# dbg-prog-counter.net
KiCad netlist of a schematic drawn in EAGLE
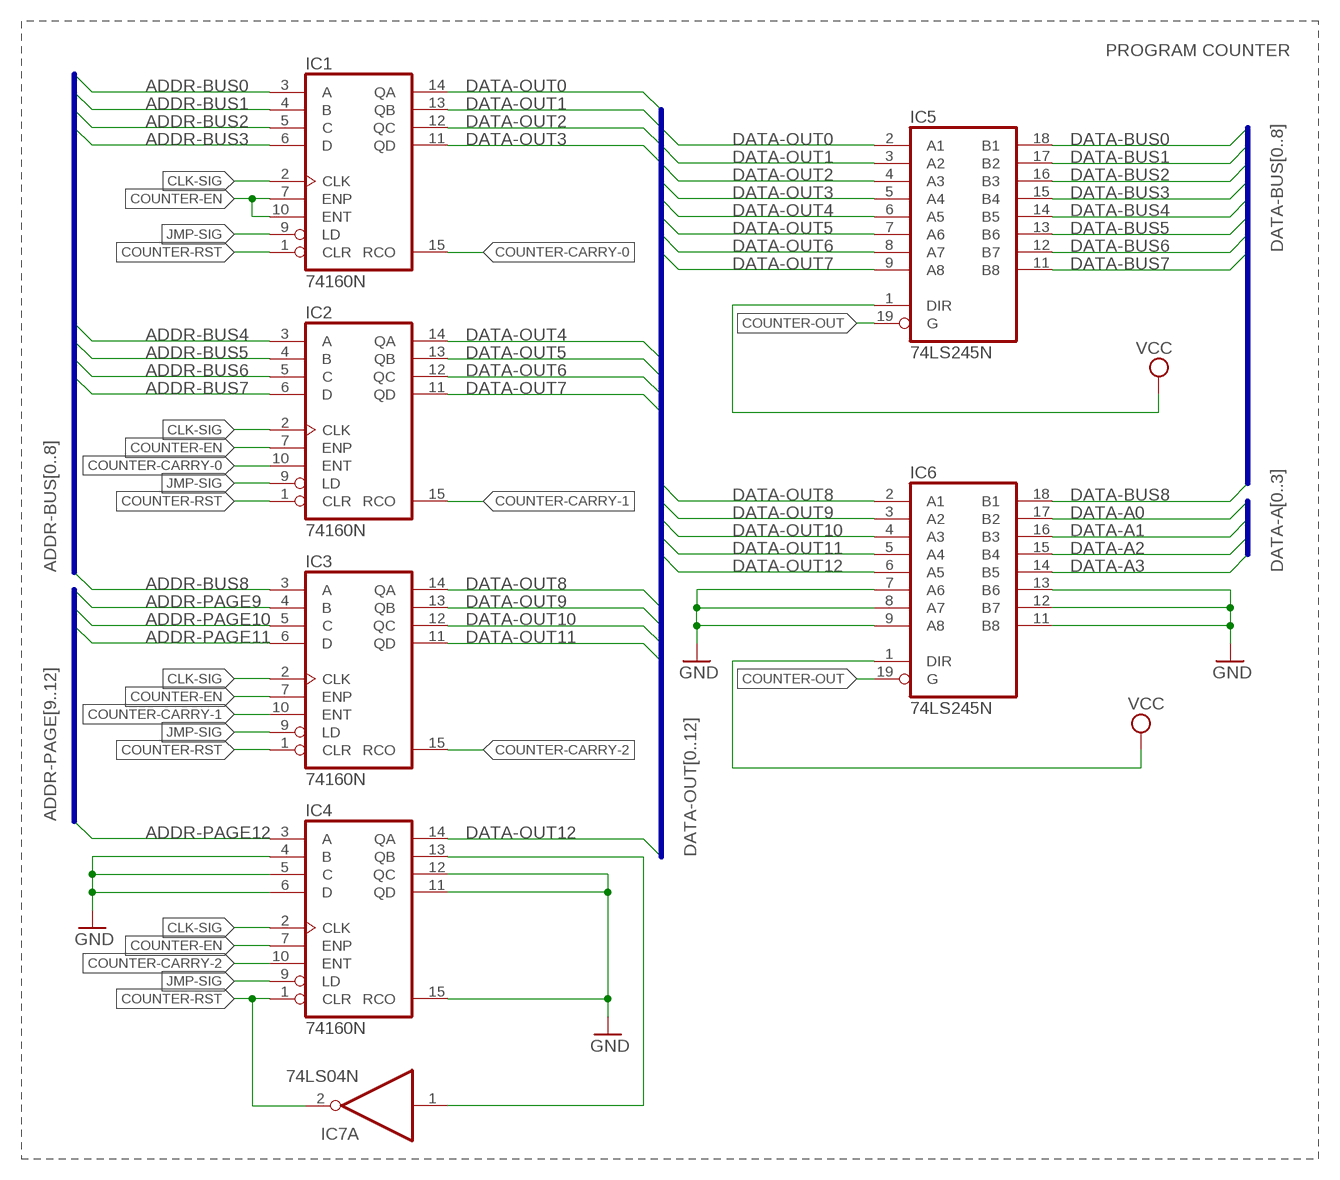
[diagram p0: schematic, sheet 1]

(export (version "E")
  (design (tool "Eeschema 10.0.6"))
  (components
    (comp (ref "IC1")
      (value "74160N")
      (footprint "eagle-import:DIL16")
      (libsource (lib "eagle-import") (part "74160N"))
    )
    (comp (ref "IC2")
      (value "74160N")
      (footprint "eagle-import:DIL16")
      (libsource (lib "eagle-import") (part "74160N"))
    )
    (comp (ref "IC3")
      (value "74160N")
      (footprint "eagle-import:DIL16")
      (libsource (lib "eagle-import") (part "74160N"))
    )
    (comp (ref "IC4")
      (value "74160N")
      (footprint "eagle-import:DIL16")
      (libsource (lib "eagle-import") (part "74160N"))
    )
    (comp (ref "IC5")
      (value "74LS245N")
      (footprint "eagle-import:DIL20")
      (libsource (lib "eagle-import") (part "74245NLS"))
    )
    (comp (ref "IC6")
      (value "74LS245N")
      (footprint "eagle-import:DIL20")
      (libsource (lib "eagle-import") (part "74245NLS"))
    )
    (comp (ref "IC7")
      (value "74LS04N")
      (footprint "eagle-import:DIL14")
      (libsource (lib "eagle-import") (part "7404NLS"))
    )
  )
  (nets
    (net (code "1") (name "/ADDR-BUS0") (class "Default")
      (node (ref "IC1") (pin "3") (pinfunction "A_3") (pintype "input"))
    )
    (net (code "2") (name "/ADDR-BUS1") (class "Default")
      (node (ref "IC1") (pin "4") (pinfunction "B_4") (pintype "input"))
    )
    (net (code "3") (name "/ADDR-BUS2") (class "Default")
      (node (ref "IC1") (pin "5") (pinfunction "C_5") (pintype "input"))
    )
    (net (code "4") (name "/ADDR-BUS3") (class "Default")
      (node (ref "IC1") (pin "6") (pinfunction "D_6") (pintype "input"))
    )
    (net (code "5") (name "/ADDR-BUS4") (class "Default")
      (node (ref "IC2") (pin "3") (pinfunction "A_3") (pintype "input"))
    )
    (net (code "6") (name "/ADDR-BUS5") (class "Default")
      (node (ref "IC2") (pin "4") (pinfunction "B_4") (pintype "input"))
    )
    (net (code "7") (name "/ADDR-BUS6") (class "Default")
      (node (ref "IC2") (pin "5") (pinfunction "C_5") (pintype "input"))
    )
    (net (code "8") (name "/ADDR-BUS7") (class "Default")
      (node (ref "IC2") (pin "6") (pinfunction "D_6") (pintype "input"))
    )
    (net (code "9") (name "/ADDR-BUS8") (class "Default")
      (node (ref "IC3") (pin "3") (pinfunction "A_3") (pintype "input"))
    )
    (net (code "11") (name "/ADDR-PAGE9") (class "Default")
      (node (ref "IC3") (pin "4") (pinfunction "B_4") (pintype "input"))
    )
    (net (code "12") (name "/ADDR-PAGE10") (class "Default")
      (node (ref "IC3") (pin "5") (pinfunction "C_5") (pintype "input"))
    )
    (net (code "13") (name "/ADDR-PAGE11") (class "Default")
      (node (ref "IC3") (pin "6") (pinfunction "D_6") (pintype "input"))
    )
    (net (code "14") (name "/ADDR-PAGE12") (class "Default")
      (node (ref "IC4") (pin "3") (pinfunction "A_3") (pintype "input"))
    )
    (net (code "16") (name "/DATA-A0") (class "Default")
      (node (ref "IC6") (pin "17") (pinfunction "B2_17") (pintype "bidirectional"))
    )
    (net (code "17") (name "/DATA-A1") (class "Default")
      (node (ref "IC6") (pin "16") (pinfunction "B3_16") (pintype "bidirectional"))
    )
    (net (code "18") (name "/DATA-A2") (class "Default")
      (node (ref "IC6") (pin "15") (pinfunction "B4_15") (pintype "bidirectional"))
    )
    (net (code "19") (name "/DATA-A3") (class "Default")
      (node (ref "IC6") (pin "14") (pinfunction "B5_14") (pintype "bidirectional"))
    )
    (net (code "21") (name "/DATA-BUS0") (class "Default")
      (node (ref "IC5") (pin "18") (pinfunction "B1_18") (pintype "bidirectional"))
    )
    (net (code "22") (name "/DATA-BUS1") (class "Default")
      (node (ref "IC5") (pin "17") (pinfunction "B2_17") (pintype "bidirectional"))
    )
    (net (code "23") (name "/DATA-BUS2") (class "Default")
      (node (ref "IC5") (pin "16") (pinfunction "B3_16") (pintype "bidirectional"))
    )
    (net (code "24") (name "/DATA-BUS3") (class "Default")
      (node (ref "IC5") (pin "15") (pinfunction "B4_15") (pintype "bidirectional"))
    )
    (net (code "25") (name "/DATA-BUS4") (class "Default")
      (node (ref "IC5") (pin "14") (pinfunction "B5_14") (pintype "bidirectional"))
    )
    (net (code "26") (name "/DATA-BUS5") (class "Default")
      (node (ref "IC5") (pin "13") (pinfunction "B6_13") (pintype "bidirectional"))
    )
    (net (code "27") (name "/DATA-BUS6") (class "Default")
      (node (ref "IC5") (pin "12") (pinfunction "B7_12") (pintype "bidirectional"))
    )
    (net (code "28") (name "/DATA-BUS7") (class "Default")
      (node (ref "IC5") (pin "11") (pinfunction "B8_11") (pintype "bidirectional"))
    )
    (net (code "29") (name "/DATA-BUS8") (class "Default")
      (node (ref "IC6") (pin "18") (pinfunction "B1_18") (pintype "bidirectional"))
    )
    (net (code "31") (name "/DATA-OUT0") (class "Default")
      (node (ref "IC1") (pin "14") (pinfunction "QA_14") (pintype "output"))
      (node (ref "IC5") (pin "2") (pinfunction "A1_2") (pintype "bidirectional"))
    )
    (net (code "32") (name "/DATA-OUT1") (class "Default")
      (node (ref "IC1") (pin "13") (pinfunction "QB_13") (pintype "output"))
      (node (ref "IC5") (pin "3") (pinfunction "A2_3") (pintype "bidirectional"))
    )
    (net (code "33") (name "/DATA-OUT2") (class "Default")
      (node (ref "IC1") (pin "12") (pinfunction "QC_12") (pintype "output"))
      (node (ref "IC5") (pin "4") (pinfunction "A3_4") (pintype "bidirectional"))
    )
    (net (code "34") (name "/DATA-OUT3") (class "Default")
      (node (ref "IC1") (pin "11") (pinfunction "QD_11") (pintype "output"))
      (node (ref "IC5") (pin "5") (pinfunction "A4_5") (pintype "bidirectional"))
    )
    (net (code "35") (name "/DATA-OUT4") (class "Default")
      (node (ref "IC2") (pin "14") (pinfunction "QA_14") (pintype "output"))
      (node (ref "IC5") (pin "6") (pinfunction "A5_6") (pintype "bidirectional"))
    )
    (net (code "36") (name "/DATA-OUT5") (class "Default")
      (node (ref "IC2") (pin "13") (pinfunction "QB_13") (pintype "output"))
      (node (ref "IC5") (pin "7") (pinfunction "A6_7") (pintype "bidirectional"))
    )
    (net (code "37") (name "/DATA-OUT6") (class "Default")
      (node (ref "IC2") (pin "12") (pinfunction "QC_12") (pintype "output"))
      (node (ref "IC5") (pin "8") (pinfunction "A7_8") (pintype "bidirectional"))
    )
    (net (code "38") (name "/DATA-OUT7") (class "Default")
      (node (ref "IC2") (pin "11") (pinfunction "QD_11") (pintype "output"))
      (node (ref "IC5") (pin "9") (pinfunction "A8_9") (pintype "bidirectional"))
    )
    (net (code "39") (name "/DATA-OUT8") (class "Default")
      (node (ref "IC3") (pin "14") (pinfunction "QA_14") (pintype "output"))
      (node (ref "IC6") (pin "2") (pinfunction "A1_2") (pintype "bidirectional"))
    )
    (net (code "40") (name "/DATA-OUT9") (class "Default")
      (node (ref "IC3") (pin "13") (pinfunction "QB_13") (pintype "output"))
      (node (ref "IC6") (pin "3") (pinfunction "A2_3") (pintype "bidirectional"))
    )
    (net (code "41") (name "/DATA-OUT10") (class "Default")
      (node (ref "IC3") (pin "12") (pinfunction "QC_12") (pintype "output"))
      (node (ref "IC6") (pin "4") (pinfunction "A3_4") (pintype "bidirectional"))
    )
    (net (code "42") (name "/DATA-OUT11") (class "Default")
      (node (ref "IC3") (pin "11") (pinfunction "QD_11") (pintype "output"))
      (node (ref "IC6") (pin "5") (pinfunction "A4_5") (pintype "bidirectional"))
    )
    (net (code "43") (name "/DATA-OUT12") (class "Default")
      (node (ref "IC4") (pin "14") (pinfunction "QA_14") (pintype "output"))
      (node (ref "IC6") (pin "6") (pinfunction "A5_6") (pintype "bidirectional"))
    )
    (net (code "45") (name "CLK-SIG") (class "Default")
      (node (ref "IC1") (pin "2") (pinfunction "CLK_2") (pintype "input"))
      (node (ref "IC2") (pin "2") (pinfunction "CLK_2") (pintype "input"))
      (node (ref "IC3") (pin "2") (pinfunction "CLK_2") (pintype "input"))
      (node (ref "IC4") (pin "2") (pinfunction "CLK_2") (pintype "input"))
    )
    (net (code "46") (name "COUNTER-CARRY-0") (class "Default")
      (node (ref "IC1") (pin "15") (pinfunction "RCO_15") (pintype "output"))
      (node (ref "IC2") (pin "10") (pinfunction "ENT_10") (pintype "input"))
    )
    (net (code "47") (name "COUNTER-CARRY-1") (class "Default")
      (node (ref "IC2") (pin "15") (pinfunction "RCO_15") (pintype "output"))
      (node (ref "IC3") (pin "10") (pinfunction "ENT_10") (pintype "input"))
    )
    (net (code "48") (name "COUNTER-CARRY-2") (class "Default")
      (node (ref "IC3") (pin "15") (pinfunction "RCO_15") (pintype "output"))
      (node (ref "IC4") (pin "10") (pinfunction "ENT_10") (pintype "input"))
    )
    (net (code "49") (name "COUNTER-EN") (class "Default")
      (node (ref "IC1") (pin "10") (pinfunction "ENT_10") (pintype "input"))
      (node (ref "IC1") (pin "7") (pinfunction "ENP_7") (pintype "input"))
      (node (ref "IC2") (pin "7") (pinfunction "ENP_7") (pintype "input"))
      (node (ref "IC3") (pin "7") (pinfunction "ENP_7") (pintype "input"))
      (node (ref "IC4") (pin "7") (pinfunction "ENP_7") (pintype "input"))
    )
    (net (code "50") (name "COUNTER-OUT") (class "Default")
      (node (ref "IC5") (pin "19") (pinfunction "G_19") (pintype "input"))
      (node (ref "IC6") (pin "19") (pinfunction "G_19") (pintype "input"))
    )
    (net (code "51") (name "COUNTER-RST") (class "Default")
      (node (ref "IC1") (pin "1") (pinfunction "CLR_1") (pintype "input"))
      (node (ref "IC2") (pin "1") (pinfunction "CLR_1") (pintype "input"))
      (node (ref "IC3") (pin "1") (pinfunction "CLR_1") (pintype "input"))
      (node (ref "IC4") (pin "1") (pinfunction "CLR_1") (pintype "input"))
      (node (ref "IC7") (pin "2") (pinfunction "O_2") (pintype "output"))
    )
    (net (code "52") (name "GND") (class "Default")
      (node (ref "IC4") (pin "11") (pinfunction "QD_11") (pintype "output"))
      (node (ref "IC4") (pin "12") (pinfunction "QC_12") (pintype "output"))
      (node (ref "IC4") (pin "15") (pinfunction "RCO_15") (pintype "output"))
      (node (ref "IC4") (pin "4") (pinfunction "B_4") (pintype "input"))
      (node (ref "IC4") (pin "5") (pinfunction "C_5") (pintype "input"))
      (node (ref "IC4") (pin "6") (pinfunction "D_6") (pintype "input"))
      (node (ref "IC6") (pin "11") (pinfunction "B8_11") (pintype "bidirectional"))
      (node (ref "IC6") (pin "12") (pinfunction "B7_12") (pintype "bidirectional"))
      (node (ref "IC6") (pin "13") (pinfunction "B6_13") (pintype "bidirectional"))
      (node (ref "IC6") (pin "7") (pinfunction "A6_7") (pintype "bidirectional"))
      (node (ref "IC6") (pin "8") (pinfunction "A7_8") (pintype "bidirectional"))
      (node (ref "IC6") (pin "9") (pinfunction "A8_9") (pintype "bidirectional"))
    )
    (net (code "53") (name "JMP-SIG") (class "Default")
      (node (ref "IC1") (pin "9") (pinfunction "LD_9") (pintype "input"))
      (node (ref "IC2") (pin "9") (pinfunction "LD_9") (pintype "input"))
      (node (ref "IC3") (pin "9") (pinfunction "LD_9") (pintype "input"))
      (node (ref "IC4") (pin "9") (pinfunction "LD_9") (pintype "input"))
    )
    (net (code "54") (name "Net-(IC4A-QB)") (class "Default")
      (node (ref "IC4") (pin "13") (pinfunction "QB_13") (pintype "output"))
      (node (ref "IC7") (pin "1") (pinfunction "I_1") (pintype "input"))
    )
    (net (code "55") (name "VCC") (class "Default")
      (node (ref "IC5") (pin "1") (pinfunction "DIR_1") (pintype "input"))
      (node (ref "IC6") (pin "1") (pinfunction "DIR_1") (pintype "input"))
    )
  )
)
